# led_flasher.net
KiCad netlist of a schematic drawn in Altium Designer
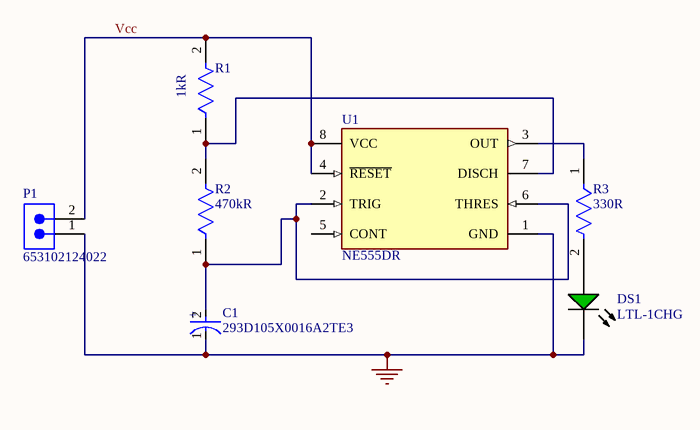
[diagram p0: led_flasher.SchDoc]

(export (version "E")
  (design (tool "Eeschema 10.0.6"))
  (components
    (comp (ref "C1")
      (value "293D105X0016A2TE3")
      (footprint "FP-293DA-MFG")
      (fields (field (name "TOLERANCE") "20%"))
      (libsource (lib "Altium Content Vault") (part "a00bbbee19879c290e62620ae7e47b1"))
    )
    (comp (ref "DS1")
      (value "LTL-1CHG")
      (footprint "LTST-LTL-1CHG-2")
      (description "LITE-ON Electronic, INC, 120 mA, 100 mW, 5 V, -55 to 100 degC, 2-Pin THD, RoHS, Bulk")
      (libsource (lib "Altium Content Vault") (part "LED_GREEN_A1K2-2"))
    )
    (comp (ref "P1")
      (value "653102124022")
      (footprint "653102124022")
      (libsource (lib "Altium Content Vault") (part "Header_Male_1R_02P"))
    )
    (comp (ref "R1")
      (value "MRS25000C1001FCT00")
      (footprint "FP-MRS25-MFG")
      (description "RES 1K OHM 0.6W 1% AXIAL")
      (fields (field (name "TOLERANCE") "1%") (field (name "RESISTANCE") "1kR"))
      (libsource (lib "Altium Content Vault") (part "1029c3af85768c4190bb7ad29bc67b5"))
    )
    (comp (ref "R2")
      (value "CRCW0805470KFKEA")
      (footprint "FP-CRCW0805-e3-IPC_C")
      (description "RES Thick Film, 470kΩ, 1%, 0.125W, 100ppm/°C, 0805")
      (fields (field (name "TOLERANCE") "1%") (field (name "RESISTANCE") "470kR"))
      (libsource (lib "Altium Content Vault") (part "1029c3af85768c4190bb7ad29bc67b5"))
    )
    (comp (ref "R3")
      (value "CRCW0603330RFKEA")
      (footprint "FP-CRCW0603-e3-MFG")
      (description "RES Thick Film, 330Ω, 1%, 0.1W, 100ppm/°C, 0603")
      (fields (field (name "TOLERANCE") "1%") (field (name "RESISTANCE") "330R"))
      (libsource (lib "Altium Content Vault") (part "1029c3af85768c4190bb7ad29bc67b5"))
    )
    (comp (ref "U1")
      (value "NE555DR")
      (footprint "FP-D0008A-IPC_A")
      (description "IC OSC SGL TIMER 100KHZ 8-SOIC")
      (libsource (lib "Altium Content Vault") (part "a29bba90211dec1890110b94dad7d53"))
    )
  )
  (nets
    (net (code "1") (name "/Vcc") (class "Default")
      (node (ref "P1") (pin "2") (pinfunction "2_2") (pintype "passive"))
      (node (ref "R1") (pin "2") (pinfunction "2_2") (pintype "passive"))
      (node (ref "U1") (pin "4") (pinfunction "~{RESET}_4") (pintype "input"))
      (node (ref "U1") (pin "8") (pinfunction "VCC_8") (pintype "power_in"))
    )
    (net (code "2") (name "GND") (class "Default")
      (node (ref "C1") (pin "1") (pinfunction "C_1") (pintype "passive"))
      (node (ref "DS1") (pin "2") (pinfunction "K_2") (pintype "passive"))
      (node (ref "P1") (pin "1") (pinfunction "1_1") (pintype "passive"))
      (node (ref "U1") (pin "1") (pinfunction "GND_1") (pintype "power_in"))
    )
    (net (code "3") (name "Net-(C1-A)") (class "Default")
      (node (ref "C1") (pin "2") (pinfunction "A_2") (pintype "passive"))
      (node (ref "R2") (pin "1") (pinfunction "1_1") (pintype "passive"))
      (node (ref "U1") (pin "2") (pinfunction "TRIG_2") (pintype "input"))
      (node (ref "U1") (pin "6") (pinfunction "THRES_6") (pintype "input"))
    )
    (net (code "4") (name "Net-(DS1-A)") (class "Default")
      (node (ref "DS1") (pin "1") (pinfunction "A_1") (pintype "passive"))
      (node (ref "R3") (pin "2") (pinfunction "2_2") (pintype "passive"))
    )
    (net (code "5") (name "Net-(U1-DISCH)") (class "Default")
      (node (ref "R1") (pin "1") (pinfunction "1_1") (pintype "passive"))
      (node (ref "R2") (pin "2") (pinfunction "2_2") (pintype "passive"))
      (node (ref "U1") (pin "7") (pinfunction "DISCH_7") (pintype "open_collector"))
    )
    (net (code "6") (name "Net-(U1-OUT)") (class "Default")
      (node (ref "R3") (pin "1") (pinfunction "1_1") (pintype "passive"))
      (node (ref "U1") (pin "3") (pinfunction "OUT_3") (pintype "output"))
    )
    (net (code "7") (name "unconnected-(U1-CONT-Pad5)") (class "Default")
      (node (ref "U1") (pin "5") (pinfunction "CONT_5") (pintype "input"))
    )
  )
)
